# main.net
KiCad netlist of a schematic drawn in Altium Designer
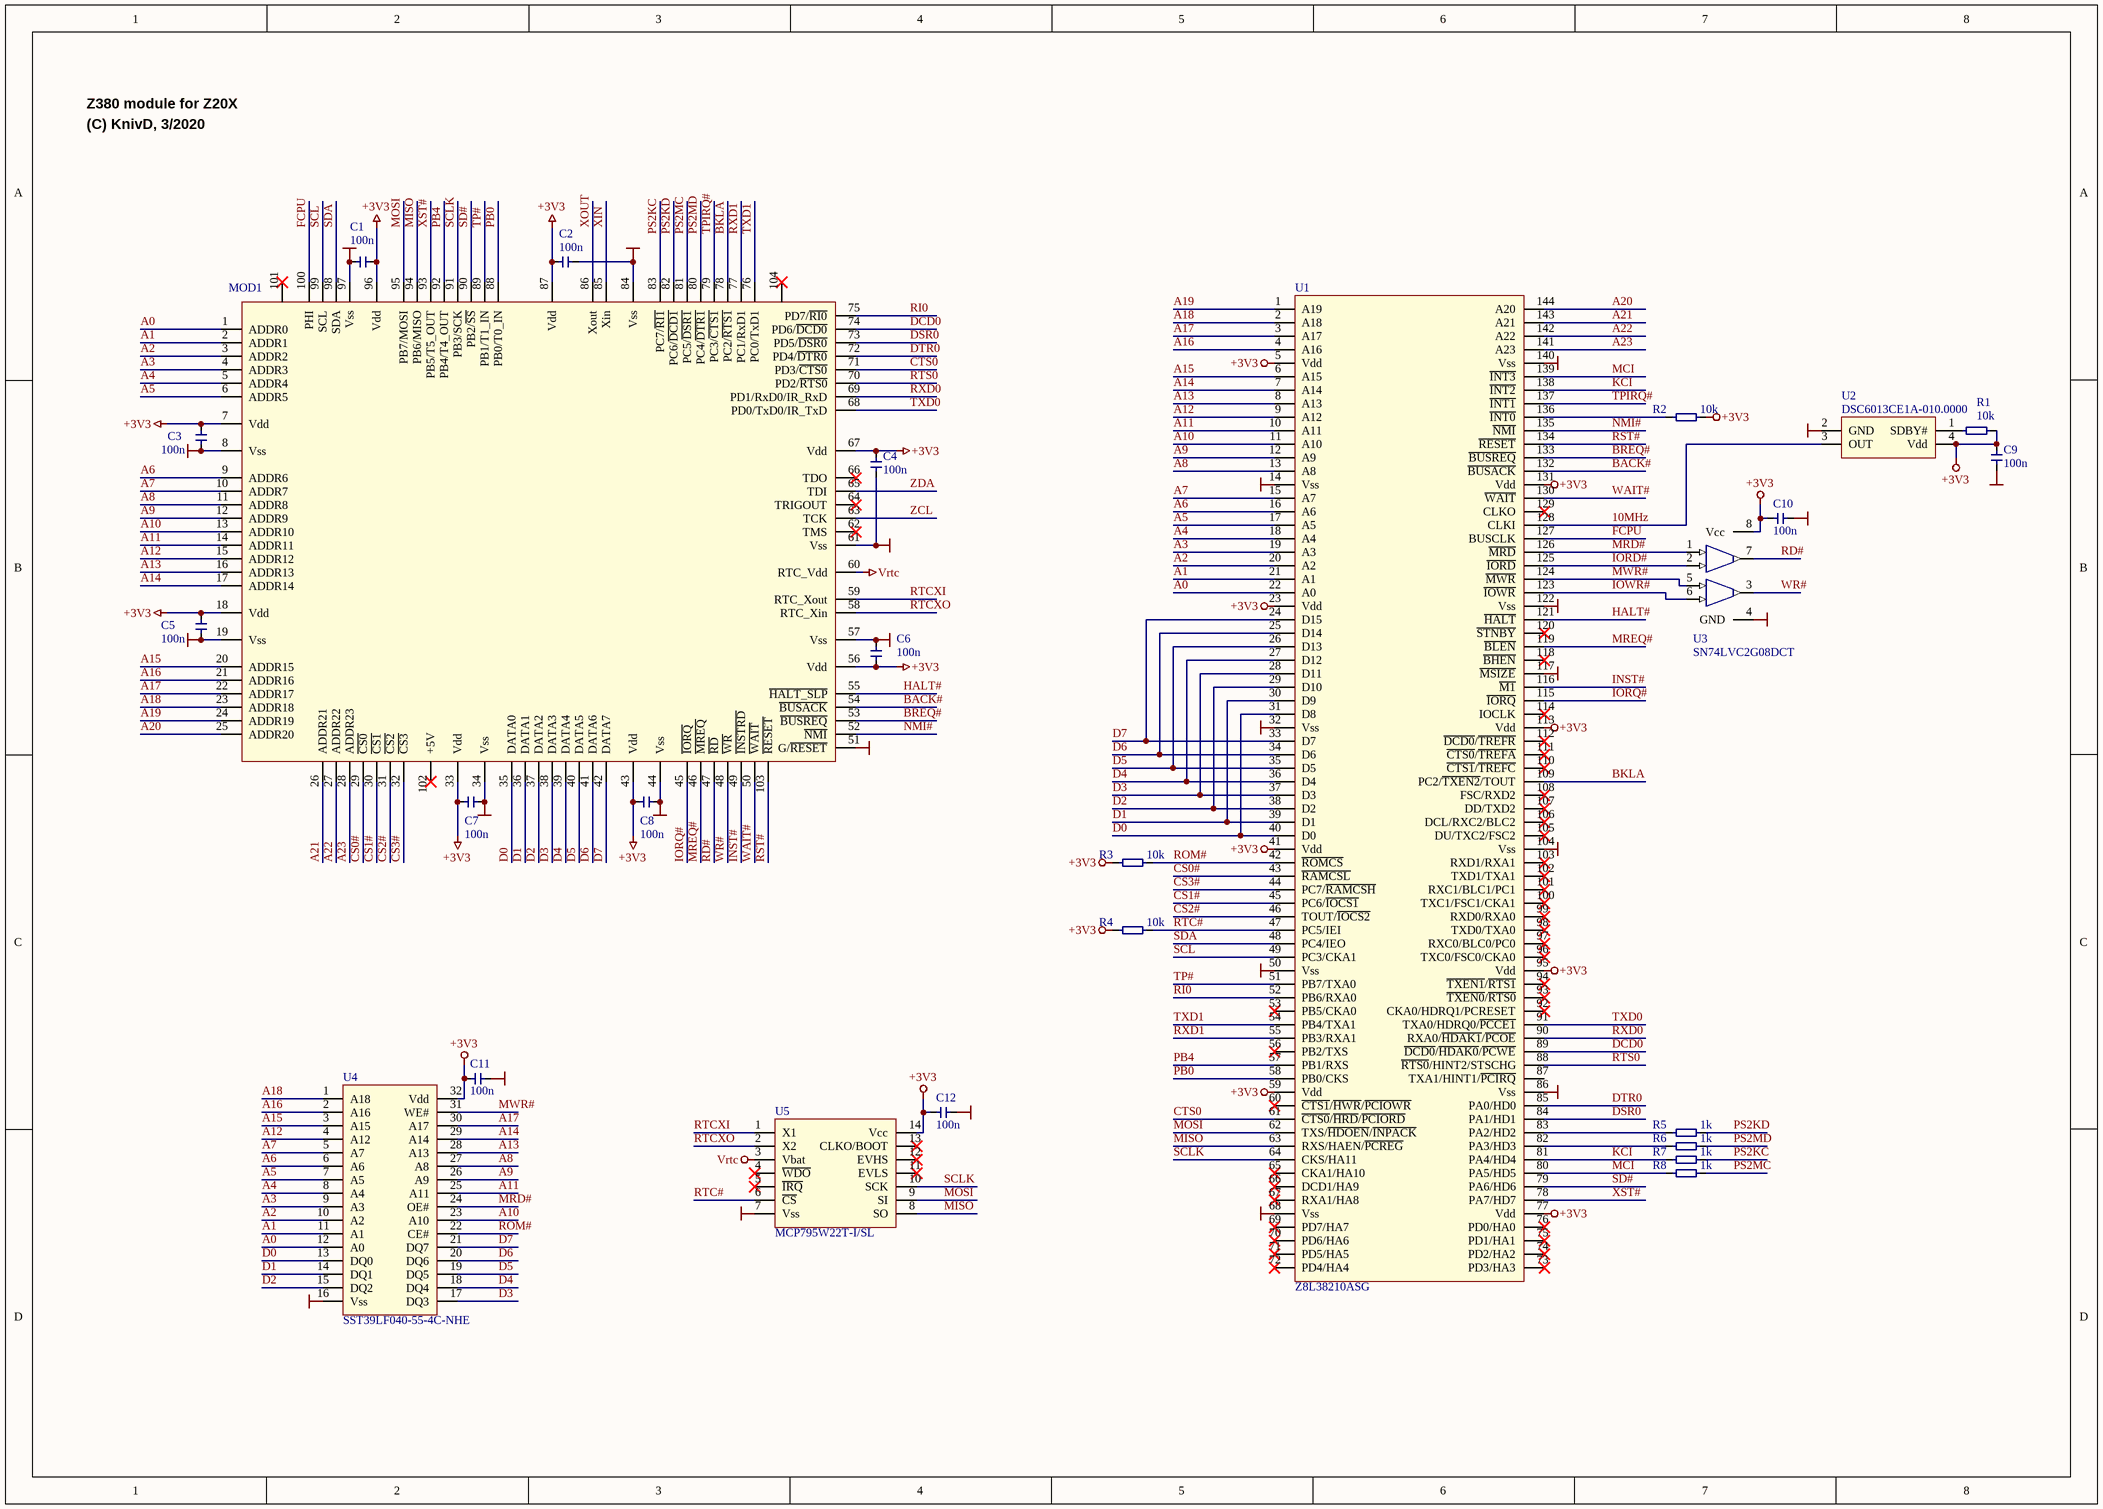
[diagram p0: main.SchDoc]

(export (version "E")
  (design (tool "Eeschema 10.0.6"))
  (components
    (comp (ref "C1")
      (value "100n")
      (footprint "_0805_CAP")
      (description "Capacitor")
      (libsource (lib "Discretes") (part "Capacitor"))
    )
    (comp (ref "C2")
      (value "100n")
      (footprint "_0805_CAP")
      (description "Capacitor")
      (libsource (lib "Discretes") (part "Capacitor"))
    )
    (comp (ref "C3")
      (value "100n")
      (footprint "_0805_CAP")
      (description "Capacitor")
      (libsource (lib "Discretes") (part "Capacitor"))
    )
    (comp (ref "C4")
      (value "100n")
      (footprint "_0805_CAP")
      (description "Capacitor")
      (libsource (lib "Discretes") (part "Capacitor"))
    )
    (comp (ref "C5")
      (value "100n")
      (footprint "_0805_CAP")
      (description "Capacitor")
      (libsource (lib "Discretes") (part "Capacitor"))
    )
    (comp (ref "C6")
      (value "100n")
      (footprint "_0805_CAP")
      (description "Capacitor")
      (libsource (lib "Discretes") (part "Capacitor"))
    )
    (comp (ref "C7")
      (value "100n")
      (footprint "_0805_CAP")
      (description "Capacitor")
      (libsource (lib "Discretes") (part "Capacitor"))
    )
    (comp (ref "C8")
      (value "100n")
      (footprint "_0805_CAP")
      (description "Capacitor")
      (libsource (lib "Discretes") (part "Capacitor"))
    )
    (comp (ref "C9")
      (value "100n")
      (footprint "_0805_CAP")
      (description "Capacitor")
      (libsource (lib "Discretes") (part "Capacitor"))
    )
    (comp (ref "C10")
      (value "100n")
      (footprint "_0805_CAP")
      (description "Capacitor")
      (libsource (lib "Discretes") (part "Capacitor"))
    )
    (comp (ref "C11")
      (value "100n")
      (footprint "_0805_CAP")
      (description "Capacitor")
      (libsource (lib "Discretes") (part "Capacitor"))
    )
    (comp (ref "C12")
      (value "100n")
      (footprint "_0805_CAP")
      (description "Capacitor")
      (libsource (lib "Discretes") (part "Capacitor"))
    )
    (comp (ref "MOD1")
      (value "Z20X CPU Module")
      (footprint "PGA100X15")
      (libsource (lib "Modules") (part "Z20X CPU Module"))
    )
    (comp (ref "R1")
      (value "10k")
      (footprint "_0805_RES")
      (description "Resistor")
      (libsource (lib "Discretes") (part "Resistor"))
    )
    (comp (ref "R2")
      (value "10k")
      (footprint "_0805_RES")
      (description "Resistor")
      (libsource (lib "Discretes") (part "Resistor"))
    )
    (comp (ref "R3")
      (value "10k")
      (footprint "_0805_RES")
      (description "Resistor")
      (libsource (lib "") (part "Resistor_1"))
    )
    (comp (ref "R4")
      (value "10k")
      (footprint "_0805_RES")
      (description "Resistor")
      (libsource (lib "") (part "Resistor_1"))
    )
    (comp (ref "R5")
      (value "1k")
      (footprint "_0805_RES")
      (description "Resistor")
      (libsource (lib "Discretes") (part "Resistor"))
    )
    (comp (ref "R6")
      (value "1k")
      (footprint "_0805_RES")
      (description "Resistor")
      (libsource (lib "Discretes") (part "Resistor"))
    )
    (comp (ref "R7")
      (value "1k")
      (footprint "_0805_RES")
      (description "Resistor")
      (libsource (lib "Discretes") (part "Resistor"))
    )
    (comp (ref "R8")
      (value "1k")
      (footprint "_0805_RES")
      (description "Resistor")
      (libsource (lib "Discretes") (part "Resistor"))
    )
    (comp (ref "U1")
      (value "Z8L38210ASG")
      (footprint "QFP50P2200X2200X170-144N")
      (description "High-Performance Data Communication Processor")
      (fields (field (name "MANUFACTURER") "Zilog"))
      (libsource (lib "IC Microcontrollers and Processors") (part "Z8x382"))
    )
    (comp (ref "U2")
      (value "DSC6013CE1A-010.0000")
      (footprint "OSC_ABRACON_ASEMPC")
      (description "Low-Power CMOS Oscillator")
      (fields (field (name "MANUFACTURER") "Microchip"))
      (libsource (lib "IC Other Functions") (part "DSC1033"))
    )
    (comp (ref "U3")
      (value "SN74LVC2G08DCT")
      (footprint "SOP65P400X130-8N")
      (description "DUAL 2-INPUT AND GATE")
      (fields (field (name "MANUFACTURER") "Texas Instruments"))
      (libsource (lib "IC Logic") (part "SN74xxx2G08"))
    )
    (comp (ref "U4")
      (value "SST39LF040-55-4C-NHE")
      (footprint "PLCC32-T/H socket")
      (description "512Kx8 CMOS Multi-Purpose Flash")
      (fields (field (name "MANUFACTURER") "Microchip"))
      (libsource (lib "IC Other Functions") (part "SST39LF/VF040 (PLCC)"))
    )
    (comp (ref "U5")
      (value "MCP795W22T-I/SL")
      (footprint "SOIC127P600X175-14N")
      (description "SPI Real-Time Clock Calendar with  Enhanced Features and Battery Switchover")
      (fields (field (name "MANUFACTURER") "Microchip"))
      (libsource (lib "IC Other Functions") (part "MCP795"))
    )
  )
  (nets
    (net (code "1") (name "+3V3") (class "Default")
      (node (ref "C1") (pin "1") (pintype "passive"))
      (node (ref "C10") (pin "2") (pintype "passive"))
      (node (ref "C11") (pin "2") (pintype "passive"))
      (node (ref "C12") (pin "2") (pintype "passive"))
      (node (ref "C2") (pin "2") (pintype "passive"))
      (node (ref "C3") (pin "1") (pintype "passive"))
      (node (ref "C4") (pin "2") (pintype "passive"))
      (node (ref "C5") (pin "1") (pintype "passive"))
      (node (ref "C6") (pin "1") (pintype "passive"))
      (node (ref "C7") (pin "1") (pintype "passive"))
      (node (ref "C8") (pin "1") (pintype "passive"))
      (node (ref "C9") (pin "2") (pintype "passive"))
      (node (ref "MOD1") (pin "18") (pinfunction "Vdd_18") (pintype "passive"))
      (node (ref "MOD1") (pin "33") (pinfunction "Vdd_33") (pintype "passive"))
      (node (ref "MOD1") (pin "43") (pinfunction "Vdd_43") (pintype "passive"))
      (node (ref "MOD1") (pin "56") (pinfunction "Vdd_56") (pintype "passive"))
      (node (ref "MOD1") (pin "67") (pinfunction "Vdd_67") (pintype "passive"))
      (node (ref "MOD1") (pin "7") (pinfunction "Vdd_7") (pintype "passive"))
      (node (ref "MOD1") (pin "87") (pinfunction "Vdd_87") (pintype "passive"))
      (node (ref "MOD1") (pin "96") (pinfunction "Vdd_96") (pintype "passive"))
      (node (ref "R1") (pin "2") (pintype "passive"))
      (node (ref "R2") (pin "2") (pintype "passive"))
      (node (ref "R3") (pin "2") (pintype "passive"))
      (node (ref "R4") (pin "2") (pintype "passive"))
      (node (ref "U1") (pin "113") (pinfunction "Vdd_113") (pintype "passive"))
      (node (ref "U1") (pin "131") (pinfunction "Vdd_131") (pintype "passive"))
      (node (ref "U1") (pin "23") (pinfunction "Vdd_23") (pintype "passive"))
      (node (ref "U1") (pin "41") (pinfunction "Vdd_41") (pintype "passive"))
      (node (ref "U1") (pin "5") (pinfunction "Vdd_5") (pintype "passive"))
      (node (ref "U1") (pin "59") (pinfunction "Vdd_59") (pintype "passive"))
      (node (ref "U1") (pin "77") (pinfunction "Vdd_77") (pintype "passive"))
      (node (ref "U1") (pin "95") (pinfunction "Vdd_95") (pintype "passive"))
      (node (ref "U2") (pin "4") (pinfunction "Vdd_4") (pintype "passive"))
      (node (ref "U3") (pin "8") (pinfunction "Vcc_8") (pintype "power_in"))
      (node (ref "U4") (pin "32") (pinfunction "Vdd_32") (pintype "passive"))
      (node (ref "U5") (pin "14") (pinfunction "Vcc_14") (pintype "passive"))
    )
    (net (code "2") (name "/10MHz") (class "Default")
      (node (ref "U1") (pin "128") (pinfunction "CLKI_128") (pintype "passive"))
      (node (ref "U2") (pin "3") (pinfunction "OUT_3") (pintype "passive"))
    )
    (net (code "3") (name "/A0") (class "Default")
      (node (ref "MOD1") (pin "1") (pinfunction "ADDR0_1") (pintype "passive"))
      (node (ref "U1") (pin "22") (pinfunction "A0_22") (pintype "passive"))
      (node (ref "U4") (pin "12") (pinfunction "A0_12") (pintype "passive"))
    )
    (net (code "4") (name "/A1") (class "Default")
      (node (ref "MOD1") (pin "2") (pinfunction "ADDR1_2") (pintype "passive"))
      (node (ref "U1") (pin "21") (pinfunction "A1_21") (pintype "passive"))
      (node (ref "U4") (pin "11") (pinfunction "A1_11") (pintype "passive"))
    )
    (net (code "5") (name "/A2") (class "Default")
      (node (ref "MOD1") (pin "3") (pinfunction "ADDR2_3") (pintype "passive"))
      (node (ref "U1") (pin "20") (pinfunction "A2_20") (pintype "passive"))
      (node (ref "U4") (pin "10") (pinfunction "A2_10") (pintype "passive"))
    )
    (net (code "6") (name "/A3") (class "Default")
      (node (ref "MOD1") (pin "4") (pinfunction "ADDR3_4") (pintype "passive"))
      (node (ref "U1") (pin "19") (pinfunction "A3_19") (pintype "passive"))
      (node (ref "U4") (pin "9") (pinfunction "A3_9") (pintype "passive"))
    )
    (net (code "7") (name "/A4") (class "Default")
      (node (ref "MOD1") (pin "5") (pinfunction "ADDR4_5") (pintype "passive"))
      (node (ref "U1") (pin "18") (pinfunction "A4_18") (pintype "passive"))
      (node (ref "U4") (pin "8") (pinfunction "A4_8") (pintype "passive"))
    )
    (net (code "8") (name "/A5") (class "Default")
      (node (ref "MOD1") (pin "6") (pinfunction "ADDR5_6") (pintype "passive"))
      (node (ref "U1") (pin "17") (pinfunction "A5_17") (pintype "passive"))
      (node (ref "U4") (pin "7") (pinfunction "A5_7") (pintype "passive"))
    )
    (net (code "9") (name "/A6") (class "Default")
      (node (ref "MOD1") (pin "9") (pinfunction "ADDR6_9") (pintype "passive"))
      (node (ref "U1") (pin "16") (pinfunction "A6_16") (pintype "passive"))
      (node (ref "U4") (pin "6") (pinfunction "A6_6") (pintype "passive"))
    )
    (net (code "10") (name "/A7") (class "Default")
      (node (ref "MOD1") (pin "10") (pinfunction "ADDR7_10") (pintype "passive"))
      (node (ref "U1") (pin "15") (pinfunction "A7_15") (pintype "passive"))
      (node (ref "U4") (pin "5") (pinfunction "A7_5") (pintype "passive"))
    )
    (net (code "11") (name "/A8") (class "Default")
      (node (ref "MOD1") (pin "11") (pinfunction "ADDR8_11") (pintype "passive"))
      (node (ref "U1") (pin "13") (pinfunction "A8_13") (pintype "passive"))
      (node (ref "U4") (pin "27") (pinfunction "A8_27") (pintype "passive"))
    )
    (net (code "12") (name "/A9") (class "Default")
      (node (ref "MOD1") (pin "12") (pinfunction "ADDR9_12") (pintype "passive"))
      (node (ref "U1") (pin "12") (pinfunction "A9_12") (pintype "passive"))
      (node (ref "U4") (pin "26") (pinfunction "A9_26") (pintype "passive"))
    )
    (net (code "13") (name "/A10") (class "Default")
      (node (ref "MOD1") (pin "13") (pinfunction "ADDR10_13") (pintype "passive"))
      (node (ref "U1") (pin "11") (pinfunction "A10_11") (pintype "passive"))
      (node (ref "U4") (pin "23") (pinfunction "A10_23") (pintype "passive"))
    )
    (net (code "14") (name "/A11") (class "Default")
      (node (ref "MOD1") (pin "14") (pinfunction "ADDR11_14") (pintype "passive"))
      (node (ref "U1") (pin "10") (pinfunction "A11_10") (pintype "passive"))
      (node (ref "U4") (pin "25") (pinfunction "A11_25") (pintype "passive"))
    )
    (net (code "15") (name "/A12") (class "Default")
      (node (ref "MOD1") (pin "15") (pinfunction "ADDR12_15") (pintype "passive"))
      (node (ref "U1") (pin "9") (pinfunction "A12_9") (pintype "passive"))
      (node (ref "U4") (pin "4") (pinfunction "A12_4") (pintype "passive"))
    )
    (net (code "16") (name "/A13") (class "Default")
      (node (ref "MOD1") (pin "16") (pinfunction "ADDR13_16") (pintype "passive"))
      (node (ref "U1") (pin "8") (pinfunction "A13_8") (pintype "passive"))
      (node (ref "U4") (pin "28") (pinfunction "A13_28") (pintype "passive"))
    )
    (net (code "17") (name "/A14") (class "Default")
      (node (ref "MOD1") (pin "17") (pinfunction "ADDR14_17") (pintype "passive"))
      (node (ref "U1") (pin "7") (pinfunction "A14_7") (pintype "passive"))
      (node (ref "U4") (pin "29") (pinfunction "A14_29") (pintype "passive"))
    )
    (net (code "18") (name "/A15") (class "Default")
      (node (ref "MOD1") (pin "20") (pinfunction "ADDR15_20") (pintype "passive"))
      (node (ref "U1") (pin "6") (pinfunction "A15_6") (pintype "passive"))
      (node (ref "U4") (pin "3") (pinfunction "A15_3") (pintype "passive"))
    )
    (net (code "19") (name "/A16") (class "Default")
      (node (ref "MOD1") (pin "21") (pinfunction "ADDR16_21") (pintype "passive"))
      (node (ref "U1") (pin "4") (pinfunction "A16_4") (pintype "passive"))
      (node (ref "U4") (pin "2") (pinfunction "A16_2") (pintype "passive"))
    )
    (net (code "20") (name "/A17") (class "Default")
      (node (ref "MOD1") (pin "22") (pinfunction "ADDR17_22") (pintype "passive"))
      (node (ref "U1") (pin "3") (pinfunction "A17_3") (pintype "passive"))
      (node (ref "U4") (pin "30") (pinfunction "A17_30") (pintype "passive"))
    )
    (net (code "21") (name "/A18") (class "Default")
      (node (ref "MOD1") (pin "23") (pinfunction "ADDR18_23") (pintype "passive"))
      (node (ref "U1") (pin "2") (pinfunction "A18_2") (pintype "passive"))
      (node (ref "U4") (pin "1") (pinfunction "A18_1") (pintype "passive"))
    )
    (net (code "22") (name "/A19") (class "Default")
      (node (ref "MOD1") (pin "24") (pinfunction "ADDR19_24") (pintype "passive"))
      (node (ref "U1") (pin "1") (pinfunction "A19_1") (pintype "passive"))
    )
    (net (code "23") (name "/A20") (class "Default")
      (node (ref "MOD1") (pin "25") (pinfunction "ADDR20_25") (pintype "passive"))
      (node (ref "U1") (pin "144") (pinfunction "A20_144") (pintype "passive"))
    )
    (net (code "24") (name "/A21") (class "Default")
      (node (ref "MOD1") (pin "26") (pinfunction "ADDR21_26") (pintype "passive"))
      (node (ref "U1") (pin "143") (pinfunction "A21_143") (pintype "passive"))
    )
    (net (code "25") (name "/A22") (class "Default")
      (node (ref "MOD1") (pin "27") (pinfunction "ADDR22_27") (pintype "passive"))
      (node (ref "U1") (pin "142") (pinfunction "A22_142") (pintype "passive"))
    )
    (net (code "26") (name "/A23") (class "Default")
      (node (ref "MOD1") (pin "28") (pinfunction "ADDR23_28") (pintype "passive"))
      (node (ref "U1") (pin "141") (pinfunction "A23_141") (pintype "passive"))
    )
    (net (code "27") (name "/BACK#") (class "Default")
      (node (ref "MOD1") (pin "54") (pinfunction "~{BUSACK}_54") (pintype "passive"))
      (node (ref "U1") (pin "132") (pinfunction "~{BUSACK}_132") (pintype "passive"))
    )
    (net (code "28") (name "/BKLA") (class "Default")
      (node (ref "MOD1") (pin "78") (pinfunction "PC2/~{RTS1}_78") (pintype "passive"))
      (node (ref "U1") (pin "109") (pinfunction "PC2/~{TXEN2}/TOUT_109") (pintype "passive"))
    )
    (net (code "29") (name "/BREQ#") (class "Default")
      (node (ref "MOD1") (pin "53") (pinfunction "~{BUSREQ}_53") (pintype "passive"))
      (node (ref "U1") (pin "133") (pinfunction "~{BUSREQ}_133") (pintype "passive"))
    )
    (net (code "30") (name "/CS0#") (class "Default")
      (node (ref "MOD1") (pin "29") (pinfunction "~{CS0}_29") (pintype "passive"))
      (node (ref "U1") (pin "43") (pinfunction "~{RAMCSL}_43") (pintype "passive"))
    )
    (net (code "31") (name "/CS1#") (class "Default")
      (node (ref "MOD1") (pin "30") (pinfunction "~{CS1}_30") (pintype "passive"))
      (node (ref "U1") (pin "45") (pinfunction "PC6/~{IOCS1}_45") (pintype "passive"))
    )
    (net (code "32") (name "/CS2#") (class "Default")
      (node (ref "MOD1") (pin "31") (pinfunction "~{CS2}_31") (pintype "passive"))
      (node (ref "U1") (pin "46") (pinfunction "TOUT/~{IOCS2}_46") (pintype "passive"))
    )
    (net (code "33") (name "/CS3#") (class "Default")
      (node (ref "MOD1") (pin "32") (pinfunction "~{CS3}_32") (pintype "passive"))
      (node (ref "U1") (pin "44") (pinfunction "PC7/~{RAMCSH}_44") (pintype "passive"))
    )
    (net (code "34") (name "/CTS0") (class "Default")
      (node (ref "MOD1") (pin "71") (pinfunction "PD3/~{CTS0}_71") (pintype "passive"))
      (node (ref "U1") (pin "61") (pinfunction "~{CTS0}/~{HRD}/~{PCIORD}_61") (pintype "passive"))
    )
    (net (code "35") (name "/D0") (class "Default")
      (node (ref "MOD1") (pin "35") (pinfunction "DATA0_35") (pintype "passive"))
      (node (ref "U1") (pin "31") (pinfunction "D8_31") (pintype "passive"))
      (node (ref "U1") (pin "40") (pinfunction "D0_40") (pintype "passive"))
      (node (ref "U4") (pin "13") (pinfunction "DQ0_13") (pintype "passive"))
    )
    (net (code "36") (name "/D1") (class "Default")
      (node (ref "MOD1") (pin "36") (pinfunction "DATA1_36") (pintype "passive"))
      (node (ref "U1") (pin "30") (pinfunction "D9_30") (pintype "passive"))
      (node (ref "U1") (pin "39") (pinfunction "D1_39") (pintype "passive"))
      (node (ref "U4") (pin "14") (pinfunction "DQ1_14") (pintype "passive"))
    )
    (net (code "37") (name "/D2") (class "Default")
      (node (ref "MOD1") (pin "37") (pinfunction "DATA2_37") (pintype "passive"))
      (node (ref "U1") (pin "29") (pinfunction "D10_29") (pintype "passive"))
      (node (ref "U1") (pin "38") (pinfunction "D2_38") (pintype "passive"))
      (node (ref "U4") (pin "15") (pinfunction "DQ2_15") (pintype "passive"))
    )
    (net (code "38") (name "/D3") (class "Default")
      (node (ref "MOD1") (pin "38") (pinfunction "DATA3_38") (pintype "passive"))
      (node (ref "U1") (pin "28") (pinfunction "D11_28") (pintype "passive"))
      (node (ref "U1") (pin "37") (pinfunction "D3_37") (pintype "passive"))
      (node (ref "U4") (pin "17") (pinfunction "DQ3_17") (pintype "passive"))
    )
    (net (code "39") (name "/D4") (class "Default")
      (node (ref "MOD1") (pin "39") (pinfunction "DATA4_39") (pintype "passive"))
      (node (ref "U1") (pin "27") (pinfunction "D12_27") (pintype "passive"))
      (node (ref "U1") (pin "36") (pinfunction "D4_36") (pintype "passive"))
      (node (ref "U4") (pin "18") (pinfunction "DQ4_18") (pintype "passive"))
    )
    (net (code "40") (name "/D5") (class "Default")
      (node (ref "MOD1") (pin "40") (pinfunction "DATA5_40") (pintype "passive"))
      (node (ref "U1") (pin "26") (pinfunction "D13_26") (pintype "passive"))
      (node (ref "U1") (pin "35") (pinfunction "D5_35") (pintype "passive"))
      (node (ref "U4") (pin "19") (pinfunction "DQ5_19") (pintype "passive"))
    )
    (net (code "41") (name "/D6") (class "Default")
      (node (ref "MOD1") (pin "41") (pinfunction "DATA6_41") (pintype "passive"))
      (node (ref "U1") (pin "25") (pinfunction "D14_25") (pintype "passive"))
      (node (ref "U1") (pin "34") (pinfunction "D6_34") (pintype "passive"))
      (node (ref "U4") (pin "20") (pinfunction "DQ6_20") (pintype "passive"))
    )
    (net (code "42") (name "/D7") (class "Default")
      (node (ref "MOD1") (pin "42") (pinfunction "DATA7_42") (pintype "passive"))
      (node (ref "U1") (pin "24") (pinfunction "D15_24") (pintype "passive"))
      (node (ref "U1") (pin "33") (pinfunction "D7_33") (pintype "passive"))
      (node (ref "U4") (pin "21") (pinfunction "DQ7_21") (pintype "passive"))
    )
    (net (code "43") (name "/DCD0") (class "Default")
      (node (ref "MOD1") (pin "74") (pinfunction "PD6/~{DCD0}_74") (pintype "passive"))
      (node (ref "U1") (pin "89") (pinfunction "~{DCD0}/~{HDAK0}/~{PCWE}_89") (pintype "passive"))
    )
    (net (code "44") (name "/DSR0") (class "Default")
      (node (ref "MOD1") (pin "73") (pinfunction "PD5/~{DSR0}_73") (pintype "passive"))
      (node (ref "U1") (pin "84") (pinfunction "PA1/HD1_84") (pintype "passive"))
    )
    (net (code "45") (name "/DTR0") (class "Default")
      (node (ref "MOD1") (pin "72") (pinfunction "PD4/~{DTR0}_72") (pintype "passive"))
      (node (ref "U1") (pin "85") (pinfunction "PA0/HD0_85") (pintype "passive"))
    )
    (net (code "46") (name "/FCPU") (class "Default")
      (node (ref "MOD1") (pin "100") (pinfunction "PHI_100") (pintype "passive"))
      (node (ref "U1") (pin "127") (pinfunction "BUSCLK_127") (pintype "passive"))
    )
    (net (code "47") (name "/HALT#") (class "Default")
      (node (ref "MOD1") (pin "55") (pinfunction "~{HALT_SLP}_55") (pintype "passive"))
      (node (ref "U1") (pin "121") (pinfunction "~{HALT}_121") (pintype "passive"))
    )
    (net (code "48") (name "/INST#") (class "Default")
      (node (ref "MOD1") (pin "49") (pinfunction "~{INSTRD}_49") (pintype "passive"))
      (node (ref "U1") (pin "116") (pinfunction "~{M1}_116") (pintype "passive"))
    )
    (net (code "49") (name "/IORD#") (class "Default")
      (node (ref "U1") (pin "125") (pinfunction "~{IORD}_125") (pintype "passive"))
      (node (ref "U3") (pin "2") (pintype "input"))
    )
    (net (code "50") (name "/IORQ#") (class "Default")
      (node (ref "MOD1") (pin "45") (pinfunction "~{IORQ}_45") (pintype "passive"))
      (node (ref "U1") (pin "115") (pinfunction "~{IORQ}_115") (pintype "passive"))
    )
    (net (code "51") (name "/IOWR#") (class "Default")
      (node (ref "U1") (pin "123") (pinfunction "~{IOWR}_123") (pintype "passive"))
      (node (ref "U3") (pin "6") (pintype "input"))
    )
    (net (code "52") (name "/KCI") (class "Default")
      (node (ref "R7") (pin "1") (pintype "passive"))
      (node (ref "U1") (pin "138") (pinfunction "~{INT2}_138") (pintype "passive"))
      (node (ref "U1") (pin "81") (pinfunction "PA4/HD4_81") (pintype "passive"))
    )
    (net (code "53") (name "/MCI") (class "Default")
      (node (ref "R8") (pin "1") (pintype "passive"))
      (node (ref "U1") (pin "139") (pinfunction "~{INT3}_139") (pintype "passive"))
      (node (ref "U1") (pin "80") (pinfunction "PA5/HD5_80") (pintype "passive"))
    )
    (net (code "54") (name "/MISO") (class "Default")
      (node (ref "MOD1") (pin "94") (pinfunction "PB6/MISO_94") (pintype "passive"))
      (node (ref "U1") (pin "63") (pinfunction "RXS/HAEN/~{PCREG}_63") (pintype "passive"))
      (node (ref "U5") (pin "8") (pinfunction "SO_8") (pintype "passive"))
    )
    (net (code "55") (name "/MOSI") (class "Default")
      (node (ref "MOD1") (pin "95") (pinfunction "PB7/MOSI_95") (pintype "passive"))
      (node (ref "U1") (pin "62") (pinfunction "TXS/~{HDOEN}/~{INPACK}_62") (pintype "passive"))
      (node (ref "U5") (pin "9") (pinfunction "SI_9") (pintype "passive"))
    )
    (net (code "56") (name "/MRD#") (class "Default")
      (node (ref "U1") (pin "126") (pinfunction "~{MRD}_126") (pintype "passive"))
      (node (ref "U3") (pin "1") (pintype "input"))
      (node (ref "U4") (pin "24") (pinfunction "OE#_24") (pintype "passive"))
    )
    (net (code "57") (name "/MREQ#") (class "Default")
      (node (ref "MOD1") (pin "46") (pinfunction "~{MREQ}_46") (pintype "passive"))
      (node (ref "U1") (pin "119") (pinfunction "~{BLEN}_119") (pintype "passive"))
    )
    (net (code "58") (name "/MWR#") (class "Default")
      (node (ref "U1") (pin "124") (pinfunction "~{MWR}_124") (pintype "passive"))
      (node (ref "U3") (pin "5") (pintype "input"))
      (node (ref "U4") (pin "31") (pinfunction "WE#_31") (pintype "passive"))
    )
    (net (code "59") (name "/NMI#") (class "Default")
      (node (ref "MOD1") (pin "52") (pinfunction "~{NMI}_52") (pintype "passive"))
      (node (ref "U1") (pin "135") (pinfunction "~{NMI}_135") (pintype "passive"))
    )
    (net (code "60") (name "/PB0") (class "Default")
      (node (ref "MOD1") (pin "88") (pinfunction "PB0/T0_IN_88") (pintype "passive"))
      (node (ref "U1") (pin "58") (pinfunction "PB0/CKS_58") (pintype "passive"))
    )
    (net (code "61") (name "/PB4") (class "Default")
      (node (ref "MOD1") (pin "92") (pinfunction "PB4/T4_OUT_92") (pintype "passive"))
      (node (ref "U1") (pin "57") (pinfunction "PB1/RXS_57") (pintype "passive"))
    )
    (net (code "62") (name "/PS2KC") (class "Default")
      (node (ref "MOD1") (pin "83") (pinfunction "PC7/~{RI1}_83") (pintype "passive"))
      (node (ref "R7") (pin "2") (pintype "passive"))
    )
    (net (code "63") (name "/PS2KD") (class "Default")
      (node (ref "MOD1") (pin "82") (pinfunction "PC6/~{DCD1}_82") (pintype "passive"))
      (node (ref "R5") (pin "2") (pintype "passive"))
    )
    (net (code "64") (name "/PS2MC") (class "Default")
      (node (ref "MOD1") (pin "81") (pinfunction "PC5/~{DSR1}_81") (pintype "passive"))
      (node (ref "R8") (pin "2") (pintype "passive"))
    )
    (net (code "65") (name "/PS2MD") (class "Default")
      (node (ref "MOD1") (pin "80") (pinfunction "PC4/~{DTR1}_80") (pintype "passive"))
      (node (ref "R6") (pin "2") (pintype "passive"))
    )
    (net (code "66") (name "/RD#") (class "Default")
      (node (ref "MOD1") (pin "47") (pinfunction "~{RD}_47") (pintype "passive"))
      (node (ref "U3") (pin "7") (pintype "output"))
    )
    (net (code "67") (name "/RI0") (class "Default")
      (node (ref "MOD1") (pin "75") (pinfunction "PD7/~{RI0}_75") (pintype "passive"))
      (node (ref "U1") (pin "52") (pinfunction "PB6/RXA0_52") (pintype "passive"))
    )
    (net (code "68") (name "/ROM#") (class "Default")
      (node (ref "R3") (pin "1") (pintype "passive"))
      (node (ref "U1") (pin "42") (pinfunction "~{ROMCS}_42") (pintype "passive"))
      (node (ref "U4") (pin "22") (pinfunction "CE#_22") (pintype "passive"))
    )
    (net (code "69") (name "/RST#") (class "Default")
      (node (ref "MOD1") (pin "103") (pinfunction "~{RESET}_103") (pintype "passive"))
      (node (ref "U1") (pin "134") (pinfunction "~{RESET}_134") (pintype "passive"))
    )
    (net (code "70") (name "/RTC#") (class "Default")
      (node (ref "R4") (pin "1") (pintype "passive"))
      (node (ref "U1") (pin "47") (pinfunction "PC5/IEI_47") (pintype "passive"))
      (node (ref "U5") (pin "6") (pinfunction "~{CS}_6") (pintype "passive"))
    )
    (net (code "71") (name "/RTCXI") (class "Default")
      (node (ref "MOD1") (pin "59") (pinfunction "RTC_Xout_59") (pintype "passive"))
      (node (ref "U5") (pin "1") (pinfunction "X1_1") (pintype "passive"))
    )
    (net (code "72") (name "/RTCXO") (class "Default")
      (node (ref "MOD1") (pin "58") (pinfunction "RTC_Xin_58") (pintype "passive"))
      (node (ref "U5") (pin "2") (pinfunction "X2_2") (pintype "passive"))
    )
    (net (code "73") (name "/RTS0") (class "Default")
      (node (ref "MOD1") (pin "70") (pinfunction "PD2/~{RTS0}_70") (pintype "passive"))
      (node (ref "U1") (pin "88") (pinfunction "~{RTS0}/HINT2/STSCHG_88") (pintype "passive"))
    )
    (net (code "74") (name "/RXD0") (class "Default")
      (node (ref "MOD1") (pin "69") (pinfunction "PD1/RxD0/IR_RxD_69") (pintype "passive"))
      (node (ref "U1") (pin "90") (pinfunction "RXA0/~{HDAK1}/~{PCOE}_90") (pintype "passive"))
    )
    (net (code "75") (name "/RXD1") (class "Default")
      (node (ref "MOD1") (pin "77") (pinfunction "PC1/RxD1_77") (pintype "passive"))
      (node (ref "U1") (pin "55") (pinfunction "PB3/RXA1_55") (pintype "passive"))
    )
    (net (code "76") (name "/SCL") (class "Default")
      (node (ref "MOD1") (pin "99") (pinfunction "SCL_99") (pintype "passive"))
      (node (ref "U1") (pin "49") (pinfunction "PC3/CKA1_49") (pintype "passive"))
    )
    (net (code "77") (name "/SCLK") (class "Default")
      (node (ref "MOD1") (pin "91") (pinfunction "PB3/SCK_91") (pintype "passive"))
      (node (ref "U1") (pin "64") (pinfunction "CKS/HA11_64") (pintype "passive"))
      (node (ref "U5") (pin "10") (pinfunction "SCK_10") (pintype "passive"))
    )
    (net (code "78") (name "/SD#") (class "Default")
      (node (ref "MOD1") (pin "90") (pinfunction "PB2/~{SS}_90") (pintype "passive"))
      (node (ref "U1") (pin "79") (pinfunction "PA6/HD6_79") (pintype "passive"))
    )
    (net (code "79") (name "/SDA") (class "Default")
      (node (ref "MOD1") (pin "98") (pinfunction "SDA_98") (pintype "passive"))
      (node (ref "U1") (pin "48") (pinfunction "PC4/IEO_48") (pintype "passive"))
    )
    (net (code "80") (name "/TP#") (class "Default")
      (node (ref "MOD1") (pin "89") (pinfunction "PB1/T1_IN_89") (pintype "passive"))
      (node (ref "U1") (pin "51") (pinfunction "PB7/TXA0_51") (pintype "passive"))
    )
    (net (code "81") (name "/TPIRQ#") (class "Default")
      (node (ref "MOD1") (pin "79") (pinfunction "PC3/~{CTS1}_79") (pintype "passive"))
      (node (ref "U1") (pin "137") (pinfunction "~{INT1}_137") (pintype "passive"))
    )
    (net (code "82") (name "/TXD0") (class "Default")
      (node (ref "MOD1") (pin "68") (pinfunction "PD0/TxD0/IR_TxD_68") (pintype "passive"))
      (node (ref "U1") (pin "91") (pinfunction "TXA0/HDRQ0/~{PCCE1}_91") (pintype "passive"))
    )
    (net (code "83") (name "/TXD1") (class "Default")
      (node (ref "MOD1") (pin "76") (pinfunction "PC0/TxD1_76") (pintype "passive"))
      (node (ref "U1") (pin "54") (pinfunction "PB4/TXA1_54") (pintype "passive"))
    )
    (net (code "84") (name "/WAIT#") (class "Default")
      (node (ref "MOD1") (pin "50") (pinfunction "~{WAIT}_50") (pintype "passive"))
      (node (ref "U1") (pin "130") (pinfunction "~{WAIT}_130") (pintype "passive"))
    )
    (net (code "85") (name "/WR#") (class "Default")
      (node (ref "MOD1") (pin "48") (pinfunction "~{WR}_48") (pintype "passive"))
      (node (ref "U3") (pin "3") (pintype "output"))
    )
    (net (code "86") (name "/XIN") (class "Default")
      (node (ref "MOD1") (pin "85") (pinfunction "Xin_85") (pintype "passive"))
    )
    (net (code "87") (name "/XOUT") (class "Default")
      (node (ref "MOD1") (pin "86") (pinfunction "Xout_86") (pintype "passive"))
    )
    (net (code "88") (name "/XST#") (class "Default")
      (node (ref "MOD1") (pin "93") (pinfunction "PB5/T5_OUT_93") (pintype "passive"))
      (node (ref "U1") (pin "78") (pinfunction "PA7/HD7_78") (pintype "passive"))
    )
    (net (code "89") (name "/ZCL") (class "Default")
      (node (ref "MOD1") (pin "63") (pinfunction "TCK_63") (pintype "passive"))
    )
    (net (code "90") (name "/ZDA") (class "Default")
      (node (ref "MOD1") (pin "65") (pinfunction "TDI_65") (pintype "passive"))
    )
    (net (code "91") (name "GND") (class "Default")
      (node (ref "C1") (pin "2") (pintype "passive"))
      (node (ref "C10") (pin "1") (pintype "passive"))
      (node (ref "C11") (pin "1") (pintype "passive"))
      (node (ref "C12") (pin "1") (pintype "passive"))
      (node (ref "C2") (pin "1") (pintype "passive"))
      (node (ref "C3") (pin "2") (pintype "passive"))
      (node (ref "C4") (pin "1") (pintype "passive"))
      (node (ref "C5") (pin "2") (pintype "passive"))
      (node (ref "C6") (pin "2") (pintype "passive"))
      (node (ref "C7") (pin "2") (pintype "passive"))
      (node (ref "C8") (pin "2") (pintype "passive"))
      (node (ref "C9") (pin "1") (pintype "passive"))
      (node (ref "MOD1") (pin "19") (pinfunction "Vss_19") (pintype "passive"))
      (node (ref "MOD1") (pin "34") (pinfunction "Vss_34") (pintype "passive"))
      (node (ref "MOD1") (pin "44") (pinfunction "Vss_44") (pintype "passive"))
      (node (ref "MOD1") (pin "51") (pinfunction "G/~{RESET}_51") (pintype "passive"))
      (node (ref "MOD1") (pin "57") (pinfunction "Vss_57") (pintype "passive"))
      (node (ref "MOD1") (pin "61") (pinfunction "Vss_61") (pintype "passive"))
      (node (ref "MOD1") (pin "8") (pinfunction "Vss_8") (pintype "passive"))
      (node (ref "MOD1") (pin "84") (pinfunction "Vss_84") (pintype "passive"))
      (node (ref "MOD1") (pin "97") (pinfunction "Vss_97") (pintype "passive"))
      (node (ref "U1") (pin "104") (pinfunction "Vss_104") (pintype "passive"))
      (node (ref "U1") (pin "117") (pinfunction "~{MSIZE}_117") (pintype "passive"))
      (node (ref "U1") (pin "122") (pinfunction "Vss_122") (pintype "passive"))
      (node (ref "U1") (pin "14") (pinfunction "Vss_14") (pintype "passive"))
      (node (ref "U1") (pin "140") (pinfunction "Vss_140") (pintype "passive"))
      (node (ref "U1") (pin "32") (pinfunction "Vss_32") (pintype "passive"))
      (node (ref "U1") (pin "50") (pinfunction "Vss_50") (pintype "passive"))
      (node (ref "U1") (pin "68") (pinfunction "Vss_68") (pintype "passive"))
      (node (ref "U1") (pin "86") (pinfunction "Vss_86") (pintype "passive"))
      (node (ref "U2") (pin "2") (pinfunction "GND_2") (pintype "passive"))
      (node (ref "U3") (pin "4") (pinfunction "GND_4") (pintype "power_in"))
      (node (ref "U4") (pin "16") (pinfunction "Vss_16") (pintype "passive"))
      (node (ref "U5") (pin "7") (pinfunction "Vss_7") (pintype "passive"))
    )
    (net (code "92") (name "Net-(U1-PA2{slash}HD2)") (class "Default")
      (node (ref "R5") (pin "1") (pintype "passive"))
      (node (ref "U1") (pin "83") (pinfunction "PA2/HD2_83") (pintype "passive"))
    )
    (net (code "93") (name "Net-(U1-PA3{slash}HD3)") (class "Default")
      (node (ref "R6") (pin "1") (pintype "passive"))
      (node (ref "U1") (pin "82") (pinfunction "PA3/HD3_82") (pintype "passive"))
    )
    (net (code "94") (name "Net-(U1-~{INT0})") (class "Default")
      (node (ref "R2") (pin "1") (pintype "passive"))
      (node (ref "U1") (pin "136") (pinfunction "~{INT0}_136") (pintype "passive"))
    )
    (net (code "95") (name "Net-(U2-SDBY#)") (class "Default")
      (node (ref "R1") (pin "1") (pintype "passive"))
      (node (ref "U2") (pin "1") (pinfunction "SDBY#_1") (pintype "passive"))
    )
    (net (code "96") (name "Vrtc") (class "Default")
      (node (ref "MOD1") (pin "60") (pinfunction "RTC_Vdd_60") (pintype "passive"))
      (node (ref "U5") (pin "3") (pinfunction "Vbat_3") (pintype "passive"))
    )
    (net (code "97") (name "unconnected-(MOD1-+5V-Pad102)") (class "Default")
      (node (ref "MOD1") (pin "102") (pinfunction "+5V_102") (pintype "passive+no_connect"))
    )
    (net (code "98") (name "unconnected-(MOD1-Pad101)") (class "Default")
      (node (ref "MOD1") (pin "101") (pintype "passive+no_connect"))
    )
    (net (code "99") (name "unconnected-(MOD1-Pad104)") (class "Default")
      (node (ref "MOD1") (pin "104") (pintype "passive+no_connect"))
    )
    (net (code "100") (name "unconnected-(MOD1-TDO-Pad66)") (class "Default")
      (node (ref "MOD1") (pin "66") (pinfunction "TDO_66") (pintype "passive+no_connect"))
    )
    (net (code "101") (name "unconnected-(MOD1-TMS-Pad62)") (class "Default")
      (node (ref "MOD1") (pin "62") (pinfunction "TMS_62") (pintype "passive+no_connect"))
    )
    (net (code "102") (name "unconnected-(MOD1-TRIGOUT-Pad64)") (class "Default")
      (node (ref "MOD1") (pin "64") (pinfunction "TRIGOUT_64") (pintype "passive+no_connect"))
    )
    (net (code "103") (name "unconnected-(U1-CKA0{slash}HDRQ1{slash}PCRESET-Pad92)") (class "Default")
      (node (ref "U1") (pin "92") (pinfunction "CKA0/HDRQ1/PCRESET_92") (pintype "passive+no_connect"))
    )
    (net (code "104") (name "unconnected-(U1-CKA1{slash}HA10-Pad65)") (class "Default")
      (node (ref "U1") (pin "65") (pinfunction "CKA1/HA10_65") (pintype "passive+no_connect"))
    )
    (net (code "105") (name "unconnected-(U1-CLKO-Pad129)") (class "Default")
      (node (ref "U1") (pin "129") (pinfunction "CLKO_129") (pintype "passive+no_connect"))
    )
    (net (code "106") (name "unconnected-(U1-DCD1{slash}HA9-Pad66)") (class "Default")
      (node (ref "U1") (pin "66") (pinfunction "DCD1/HA9_66") (pintype "passive+no_connect"))
    )
    (net (code "107") (name "unconnected-(U1-DCL{slash}RXC2{slash}BLC2-Pad106)") (class "Default")
      (node (ref "U1") (pin "106") (pinfunction "DCL/RXC2/BLC2_106") (pintype "passive+no_connect"))
    )
    (net (code "108") (name "unconnected-(U1-DD{slash}TXD2-Pad107)") (class "Default")
      (node (ref "U1") (pin "107") (pinfunction "DD/TXD2_107") (pintype "passive+no_connect"))
    )
    (net (code "109") (name "unconnected-(U1-DU{slash}TXC2{slash}FSC2-Pad105)") (class "Default")
      (node (ref "U1") (pin "105") (pinfunction "DU/TXC2/FSC2_105") (pintype "passive+no_connect"))
    )
    (net (code "110") (name "unconnected-(U1-FSC{slash}RXD2-Pad108)") (class "Default")
      (node (ref "U1") (pin "108") (pinfunction "FSC/RXD2_108") (pintype "passive+no_connect"))
    )
    (net (code "111") (name "unconnected-(U1-IOCLK-Pad114)") (class "Default")
      (node (ref "U1") (pin "114") (pinfunction "IOCLK_114") (pintype "passive+no_connect"))
    )
    (net (code "112") (name "unconnected-(U1-PB2{slash}TXS-Pad56)") (class "Default")
      (node (ref "U1") (pin "56") (pinfunction "PB2/TXS_56") (pintype "passive+no_connect"))
    )
    (net (code "113") (name "unconnected-(U1-PB5{slash}CKA0-Pad53)") (class "Default")
      (node (ref "U1") (pin "53") (pinfunction "PB5/CKA0_53") (pintype "passive+no_connect"))
    )
    (net (code "114") (name "unconnected-(U1-PD0{slash}HA0-Pad76)") (class "Default")
      (node (ref "U1") (pin "76") (pinfunction "PD0/HA0_76") (pintype "passive+no_connect"))
    )
    (net (code "115") (name "unconnected-(U1-PD1{slash}HA1-Pad75)") (class "Default")
      (node (ref "U1") (pin "75") (pinfunction "PD1/HA1_75") (pintype "passive+no_connect"))
    )
    (net (code "116") (name "unconnected-(U1-PD2{slash}HA2-Pad74)") (class "Default")
      (node (ref "U1") (pin "74") (pinfunction "PD2/HA2_74") (pintype "passive+no_connect"))
    )
    (net (code "117") (name "unconnected-(U1-PD3{slash}HA3-Pad73)") (class "Default")
      (node (ref "U1") (pin "73") (pinfunction "PD3/HA3_73") (pintype "passive+no_connect"))
    )
    (net (code "118") (name "unconnected-(U1-PD4{slash}HA4-Pad72)") (class "Default")
      (node (ref "U1") (pin "72") (pinfunction "PD4/HA4_72") (pintype "passive+no_connect"))
    )
    (net (code "119") (name "unconnected-(U1-PD5{slash}HA5-Pad71)") (class "Default")
      (node (ref "U1") (pin "71") (pinfunction "PD5/HA5_71") (pintype "passive+no_connect"))
    )
    (net (code "120") (name "unconnected-(U1-PD6{slash}HA6-Pad70)") (class "Default")
      (node (ref "U1") (pin "70") (pinfunction "PD6/HA6_70") (pintype "passive+no_connect"))
    )
    (net (code "121") (name "unconnected-(U1-PD7{slash}HA7-Pad69)") (class "Default")
      (node (ref "U1") (pin "69") (pinfunction "PD7/HA7_69") (pintype "passive+no_connect"))
    )
    (net (code "122") (name "unconnected-(U1-RXA1{slash}HA8-Pad67)") (class "Default")
      (node (ref "U1") (pin "67") (pinfunction "RXA1/HA8_67") (pintype "passive+no_connect"))
    )
    (net (code "123") (name "unconnected-(U1-RXC0{slash}BLC0{slash}PC0-Pad97)") (class "Default")
      (node (ref "U1") (pin "97") (pinfunction "RXC0/BLC0/PC0_97") (pintype "passive+no_connect"))
    )
    (net (code "124") (name "unconnected-(U1-RXC1{slash}BLC1{slash}PC1-Pad101)") (class "Default")
      (node (ref "U1") (pin "101") (pinfunction "RXC1/BLC1/PC1_101") (pintype "passive+no_connect"))
    )
    (net (code "125") (name "unconnected-(U1-RXD0{slash}RXA0-Pad99)") (class "Default")
      (node (ref "U1") (pin "99") (pinfunction "RXD0/RXA0_99") (pintype "passive+no_connect"))
    )
    (net (code "126") (name "unconnected-(U1-RXD1{slash}RXA1-Pad103)") (class "Default")
      (node (ref "U1") (pin "103") (pinfunction "RXD1/RXA1_103") (pintype "passive+no_connect"))
    )
    (net (code "127") (name "unconnected-(U1-TXA1{slash}HINT1{slash}~{PCIRQ}-Pad87)") (class "Default")
      (node (ref "U1") (pin "87") (pinfunction "TXA1/HINT1/~{PCIRQ}_87") (pintype "passive"))
    )
    (net (code "128") (name "unconnected-(U1-TXC0{slash}FSC0{slash}CKA0-Pad96)") (class "Default")
      (node (ref "U1") (pin "96") (pinfunction "TXC0/FSC0/CKA0_96") (pintype "passive+no_connect"))
    )
    (net (code "129") (name "unconnected-(U1-TXC1{slash}FSC1{slash}CKA1-Pad100)") (class "Default")
      (node (ref "U1") (pin "100") (pinfunction "TXC1/FSC1/CKA1_100") (pintype "passive+no_connect"))
    )
    (net (code "130") (name "unconnected-(U1-TXD0{slash}TXA0-Pad98)") (class "Default")
      (node (ref "U1") (pin "98") (pinfunction "TXD0/TXA0_98") (pintype "passive+no_connect"))
    )
    (net (code "131") (name "unconnected-(U1-TXD1{slash}TXA1-Pad102)") (class "Default")
      (node (ref "U1") (pin "102") (pinfunction "TXD1/TXA1_102") (pintype "passive+no_connect"))
    )
    (net (code "132") (name "unconnected-(U1-~{BHEN}-Pad118)") (class "Default")
      (node (ref "U1") (pin "118") (pinfunction "~{BHEN}_118") (pintype "passive+no_connect"))
    )
    (net (code "133") (name "unconnected-(U1-~{CTS0}{slash}~{TREFA}-Pad111)") (class "Default")
      (node (ref "U1") (pin "111") (pinfunction "~{CTS0}/~{TREFA}_111") (pintype "passive+no_connect"))
    )
    (net (code "134") (name "unconnected-(U1-~{CTS1}{slash}~{HWR}{slash}~{PCIOWR}-Pad60)") (class "Default")
      (node (ref "U1") (pin "60") (pinfunction "~{CTS1}/~{HWR}/~{PCIOWR}_60") (pintype "passive+no_connect"))
    )
    (net (code "135") (name "unconnected-(U1-~{CTS1}{slash}~{TREFC}-Pad110)") (class "Default")
      (node (ref "U1") (pin "110") (pinfunction "~{CTS1}/~{TREFC}_110") (pintype "passive+no_connect"))
    )
    (net (code "136") (name "unconnected-(U1-~{DCD0}{slash}~{TREFR}-Pad112)") (class "Default")
      (node (ref "U1") (pin "112") (pinfunction "~{DCD0}/~{TREFR}_112") (pintype "passive+no_connect"))
    )
    (net (code "137") (name "unconnected-(U1-~{STNBY}-Pad120)") (class "Default")
      (node (ref "U1") (pin "120") (pinfunction "~{STNBY}_120") (pintype "passive+no_connect"))
    )
    (net (code "138") (name "unconnected-(U1-~{TXEN0}{slash}~{RTS0}-Pad93)") (class "Default")
      (node (ref "U1") (pin "93") (pinfunction "~{TXEN0}/~{RTS0}_93") (pintype "passive+no_connect"))
    )
    (net (code "139") (name "unconnected-(U1-~{TXEN1}{slash}~{RTS1}-Pad94)") (class "Default")
      (node (ref "U1") (pin "94") (pinfunction "~{TXEN1}/~{RTS1}_94") (pintype "passive+no_connect"))
    )
    (net (code "140") (name "unconnected-(U5-CLKO{slash}BOOT-Pad13)") (class "Default")
      (node (ref "U5") (pin "13") (pinfunction "CLKO/BOOT_13") (pintype "passive+no_connect"))
    )
    (net (code "141") (name "unconnected-(U5-EVHS-Pad12)") (class "Default")
      (node (ref "U5") (pin "12") (pinfunction "EVHS_12") (pintype "passive+no_connect"))
    )
    (net (code "142") (name "unconnected-(U5-EVLS-Pad11)") (class "Default")
      (node (ref "U5") (pin "11") (pinfunction "EVLS_11") (pintype "passive+no_connect"))
    )
    (net (code "143") (name "unconnected-(U5-~{IRQ}-Pad5)") (class "Default")
      (node (ref "U5") (pin "5") (pinfunction "~{IRQ}_5") (pintype "passive+no_connect"))
    )
    (net (code "144") (name "unconnected-(U5-~{WDO}-Pad4)") (class "Default")
      (node (ref "U5") (pin "4") (pinfunction "~{WDO}_4") (pintype "passive+no_connect"))
    )
  )
)
